# D1MTERMINAL.net
KiCad netlist of a schematic drawn in EAGLE
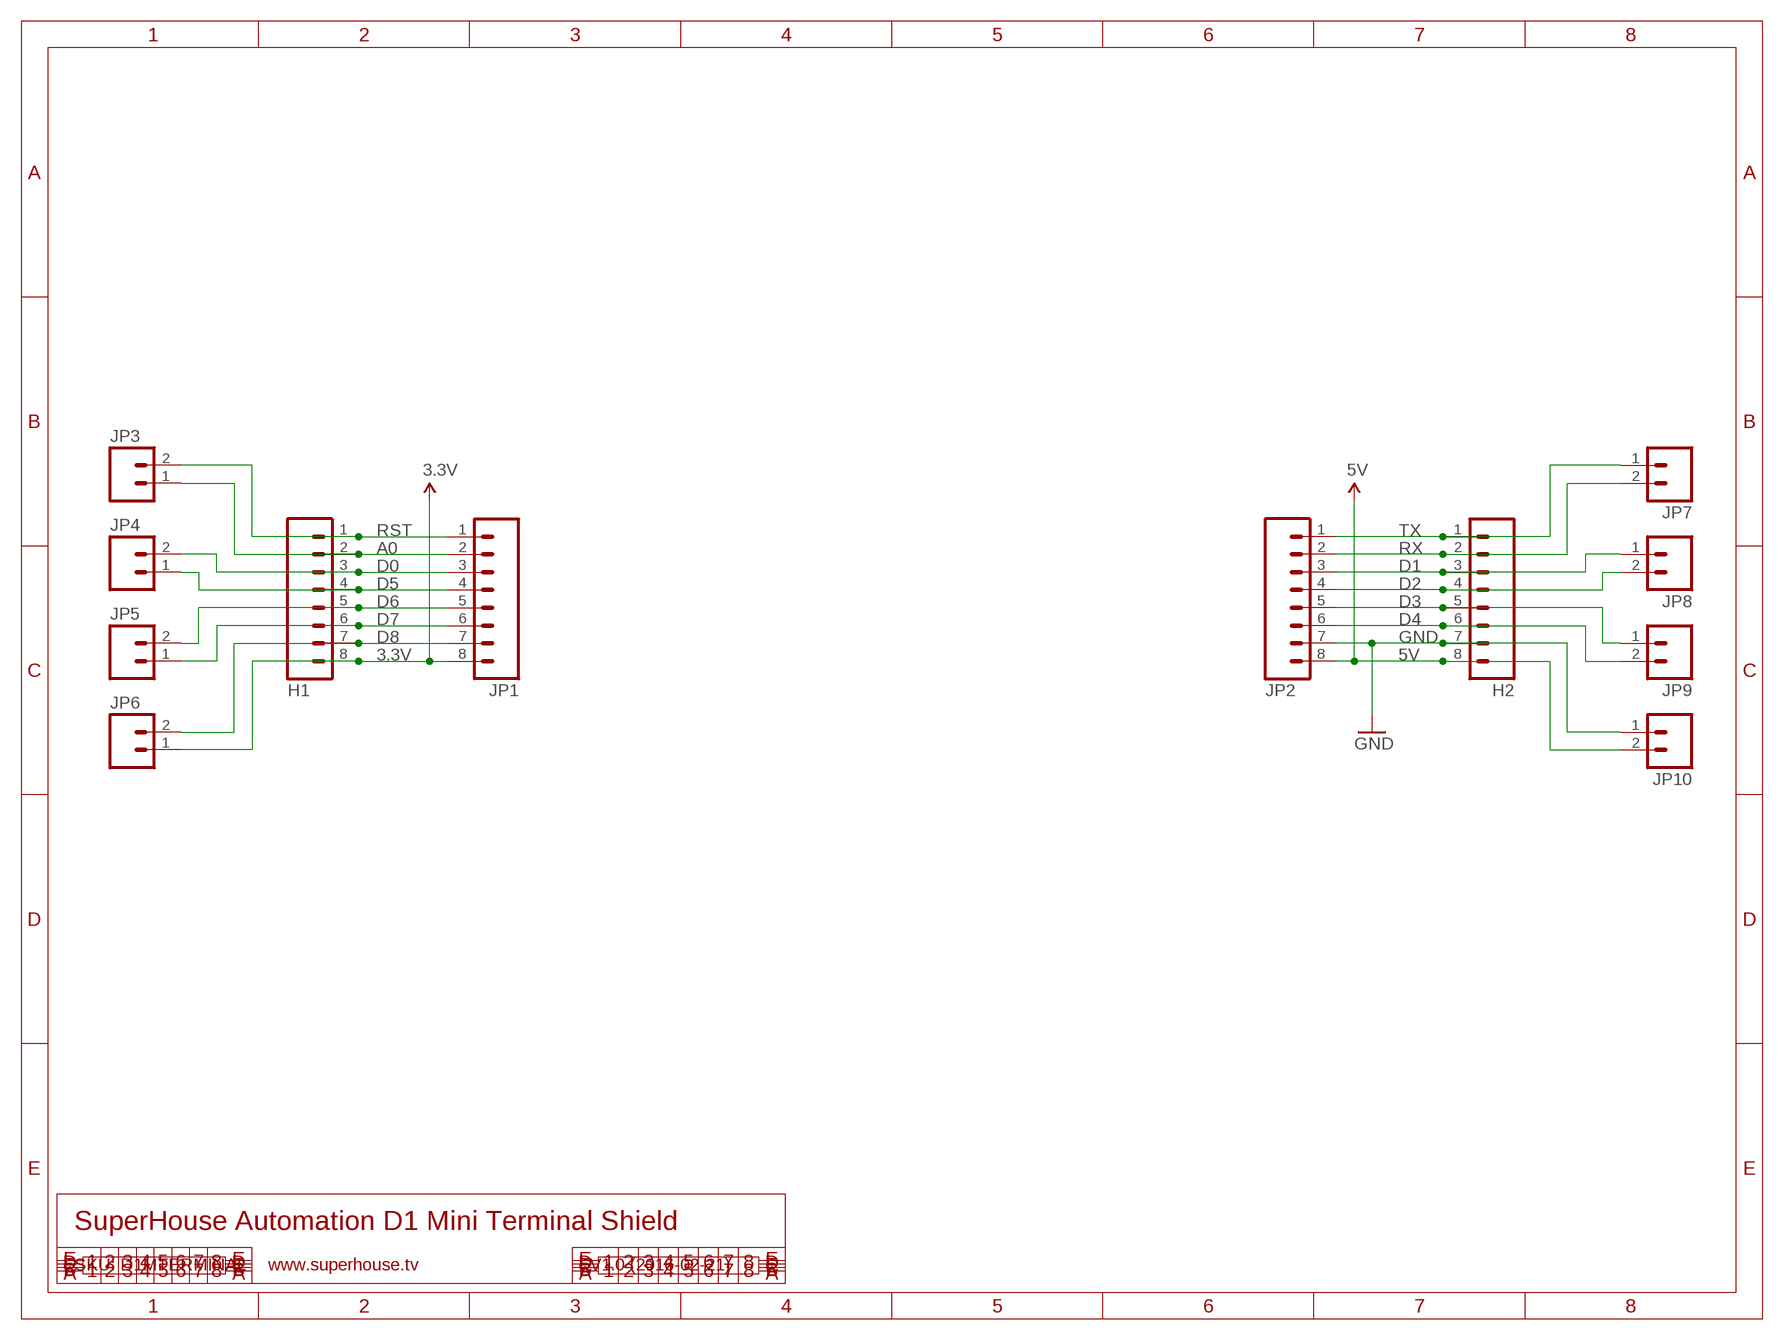
[diagram p0: schematic, sheet 1]

(export (version "E")
  (design (tool "Eeschema 10.0.6"))
  (components
    (comp (ref "H1")
      (value "M08")
      (footprint "eagle-import:1X08")
      (libsource (lib "eagle-import") (part "M08"))
    )
    (comp (ref "H2")
      (value "M08")
      (footprint "eagle-import:1X08")
      (libsource (lib "eagle-import") (part "M08"))
    )
    (comp (ref "JP1")
      (value "M08")
      (footprint "eagle-import:1X08")
      (libsource (lib "eagle-import") (part "M08"))
    )
    (comp (ref "JP2")
      (value "M08")
      (footprint "eagle-import:1X08")
      (libsource (lib "eagle-import") (part "M08"))
    )
    (comp (ref "JP3")
      (value "M023.5MM")
      (footprint "eagle-import:SCREWTERMINAL-3.5MM-2")
      (libsource (lib "eagle-import") (part "M023.5MM"))
    )
    (comp (ref "JP4")
      (value "M023.5MM")
      (footprint "eagle-import:SCREWTERMINAL-3.5MM-2")
      (libsource (lib "eagle-import") (part "M023.5MM"))
    )
    (comp (ref "JP5")
      (value "M023.5MM")
      (footprint "eagle-import:SCREWTERMINAL-3.5MM-2")
      (libsource (lib "eagle-import") (part "M023.5MM"))
    )
    (comp (ref "JP6")
      (value "M023.5MM")
      (footprint "eagle-import:SCREWTERMINAL-3.5MM-2")
      (libsource (lib "eagle-import") (part "M023.5MM"))
    )
    (comp (ref "JP7")
      (value "M023.5MM")
      (footprint "eagle-import:SCREWTERMINAL-3.5MM-2")
      (libsource (lib "eagle-import") (part "M023.5MM"))
    )
    (comp (ref "JP8")
      (value "M023.5MM")
      (footprint "eagle-import:SCREWTERMINAL-3.5MM-2")
      (libsource (lib "eagle-import") (part "M023.5MM"))
    )
    (comp (ref "JP9")
      (value "M023.5MM")
      (footprint "eagle-import:SCREWTERMINAL-3.5MM-2")
      (libsource (lib "eagle-import") (part "M023.5MM"))
    )
    (comp (ref "JP10")
      (value "M023.5MM")
      (footprint "eagle-import:SCREWTERMINAL-3.5MM-2")
      (libsource (lib "eagle-import") (part "M023.5MM"))
    )
  )
  (nets
    (net (code "1") (name "/A0") (class "Default")
      (node (ref "H1") (pin "2") (pinfunction "2_2") (pintype "passive"))
      (node (ref "JP1") (pin "2") (pinfunction "2_2") (pintype "passive"))
      (node (ref "JP3") (pin "1") (pinfunction "1_1") (pintype "passive"))
    )
    (net (code "2") (name "/D0") (class "Default")
      (node (ref "H1") (pin "3") (pinfunction "3_3") (pintype "passive"))
      (node (ref "JP1") (pin "3") (pinfunction "3_3") (pintype "passive"))
      (node (ref "JP4") (pin "2") (pinfunction "2_2") (pintype "passive"))
    )
    (net (code "3") (name "/D1") (class "Default")
      (node (ref "H2") (pin "3") (pinfunction "3_3") (pintype "passive"))
      (node (ref "JP2") (pin "3") (pinfunction "3_3") (pintype "passive"))
      (node (ref "JP8") (pin "1") (pinfunction "1_1") (pintype "passive"))
    )
    (net (code "4") (name "/D2") (class "Default")
      (node (ref "H2") (pin "4") (pinfunction "4_4") (pintype "passive"))
      (node (ref "JP2") (pin "4") (pinfunction "4_4") (pintype "passive"))
      (node (ref "JP8") (pin "2") (pinfunction "2_2") (pintype "passive"))
    )
    (net (code "5") (name "/D3") (class "Default")
      (node (ref "H2") (pin "5") (pinfunction "5_5") (pintype "passive"))
      (node (ref "JP2") (pin "5") (pinfunction "5_5") (pintype "passive"))
      (node (ref "JP9") (pin "1") (pinfunction "1_1") (pintype "passive"))
    )
    (net (code "6") (name "/D4") (class "Default")
      (node (ref "H2") (pin "6") (pinfunction "6_6") (pintype "passive"))
      (node (ref "JP2") (pin "6") (pinfunction "6_6") (pintype "passive"))
      (node (ref "JP9") (pin "2") (pinfunction "2_2") (pintype "passive"))
    )
    (net (code "7") (name "/D5") (class "Default")
      (node (ref "H1") (pin "4") (pinfunction "4_4") (pintype "passive"))
      (node (ref "JP1") (pin "4") (pinfunction "4_4") (pintype "passive"))
      (node (ref "JP4") (pin "1") (pinfunction "1_1") (pintype "passive"))
    )
    (net (code "8") (name "/D6") (class "Default")
      (node (ref "H1") (pin "5") (pinfunction "5_5") (pintype "passive"))
      (node (ref "JP1") (pin "5") (pinfunction "5_5") (pintype "passive"))
      (node (ref "JP5") (pin "2") (pinfunction "2_2") (pintype "passive"))
    )
    (net (code "9") (name "/D7") (class "Default")
      (node (ref "H1") (pin "6") (pinfunction "6_6") (pintype "passive"))
      (node (ref "JP1") (pin "6") (pinfunction "6_6") (pintype "passive"))
      (node (ref "JP5") (pin "1") (pinfunction "1_1") (pintype "passive"))
    )
    (net (code "10") (name "/D8") (class "Default")
      (node (ref "H1") (pin "7") (pinfunction "7_7") (pintype "passive"))
      (node (ref "JP1") (pin "7") (pinfunction "7_7") (pintype "passive"))
      (node (ref "JP6") (pin "2") (pinfunction "2_2") (pintype "passive"))
    )
    (net (code "11") (name "/RST") (class "Default")
      (node (ref "H1") (pin "1") (pinfunction "1_1") (pintype "passive"))
      (node (ref "JP1") (pin "1") (pinfunction "1_1") (pintype "passive"))
      (node (ref "JP3") (pin "2") (pinfunction "2_2") (pintype "passive"))
    )
    (net (code "12") (name "/RX") (class "Default")
      (node (ref "H2") (pin "2") (pinfunction "2_2") (pintype "passive"))
      (node (ref "JP2") (pin "2") (pinfunction "2_2") (pintype "passive"))
      (node (ref "JP7") (pin "2") (pinfunction "2_2") (pintype "passive"))
    )
    (net (code "13") (name "/TX") (class "Default")
      (node (ref "H2") (pin "1") (pinfunction "1_1") (pintype "passive"))
      (node (ref "JP2") (pin "1") (pinfunction "1_1") (pintype "passive"))
      (node (ref "JP7") (pin "1") (pinfunction "1_1") (pintype "passive"))
    )
    (net (code "14") (name "3.3V") (class "Default")
      (node (ref "H1") (pin "8") (pinfunction "8_8") (pintype "passive"))
      (node (ref "JP1") (pin "8") (pinfunction "8_8") (pintype "passive"))
      (node (ref "JP6") (pin "1") (pinfunction "1_1") (pintype "passive"))
    )
    (net (code "15") (name "5V") (class "Default")
      (node (ref "H2") (pin "8") (pinfunction "8_8") (pintype "passive"))
      (node (ref "JP10") (pin "2") (pinfunction "2_2") (pintype "passive"))
      (node (ref "JP2") (pin "8") (pinfunction "8_8") (pintype "passive"))
    )
    (net (code "16") (name "GND") (class "Default")
      (node (ref "H2") (pin "7") (pinfunction "7_7") (pintype "passive"))
      (node (ref "JP10") (pin "1") (pinfunction "1_1") (pintype "passive"))
      (node (ref "JP2") (pin "7") (pinfunction "7_7") (pintype "passive"))
    )
  )
)
